# RF_433MHz.net
KiCad netlist of a schematic drawn in Altium Designer
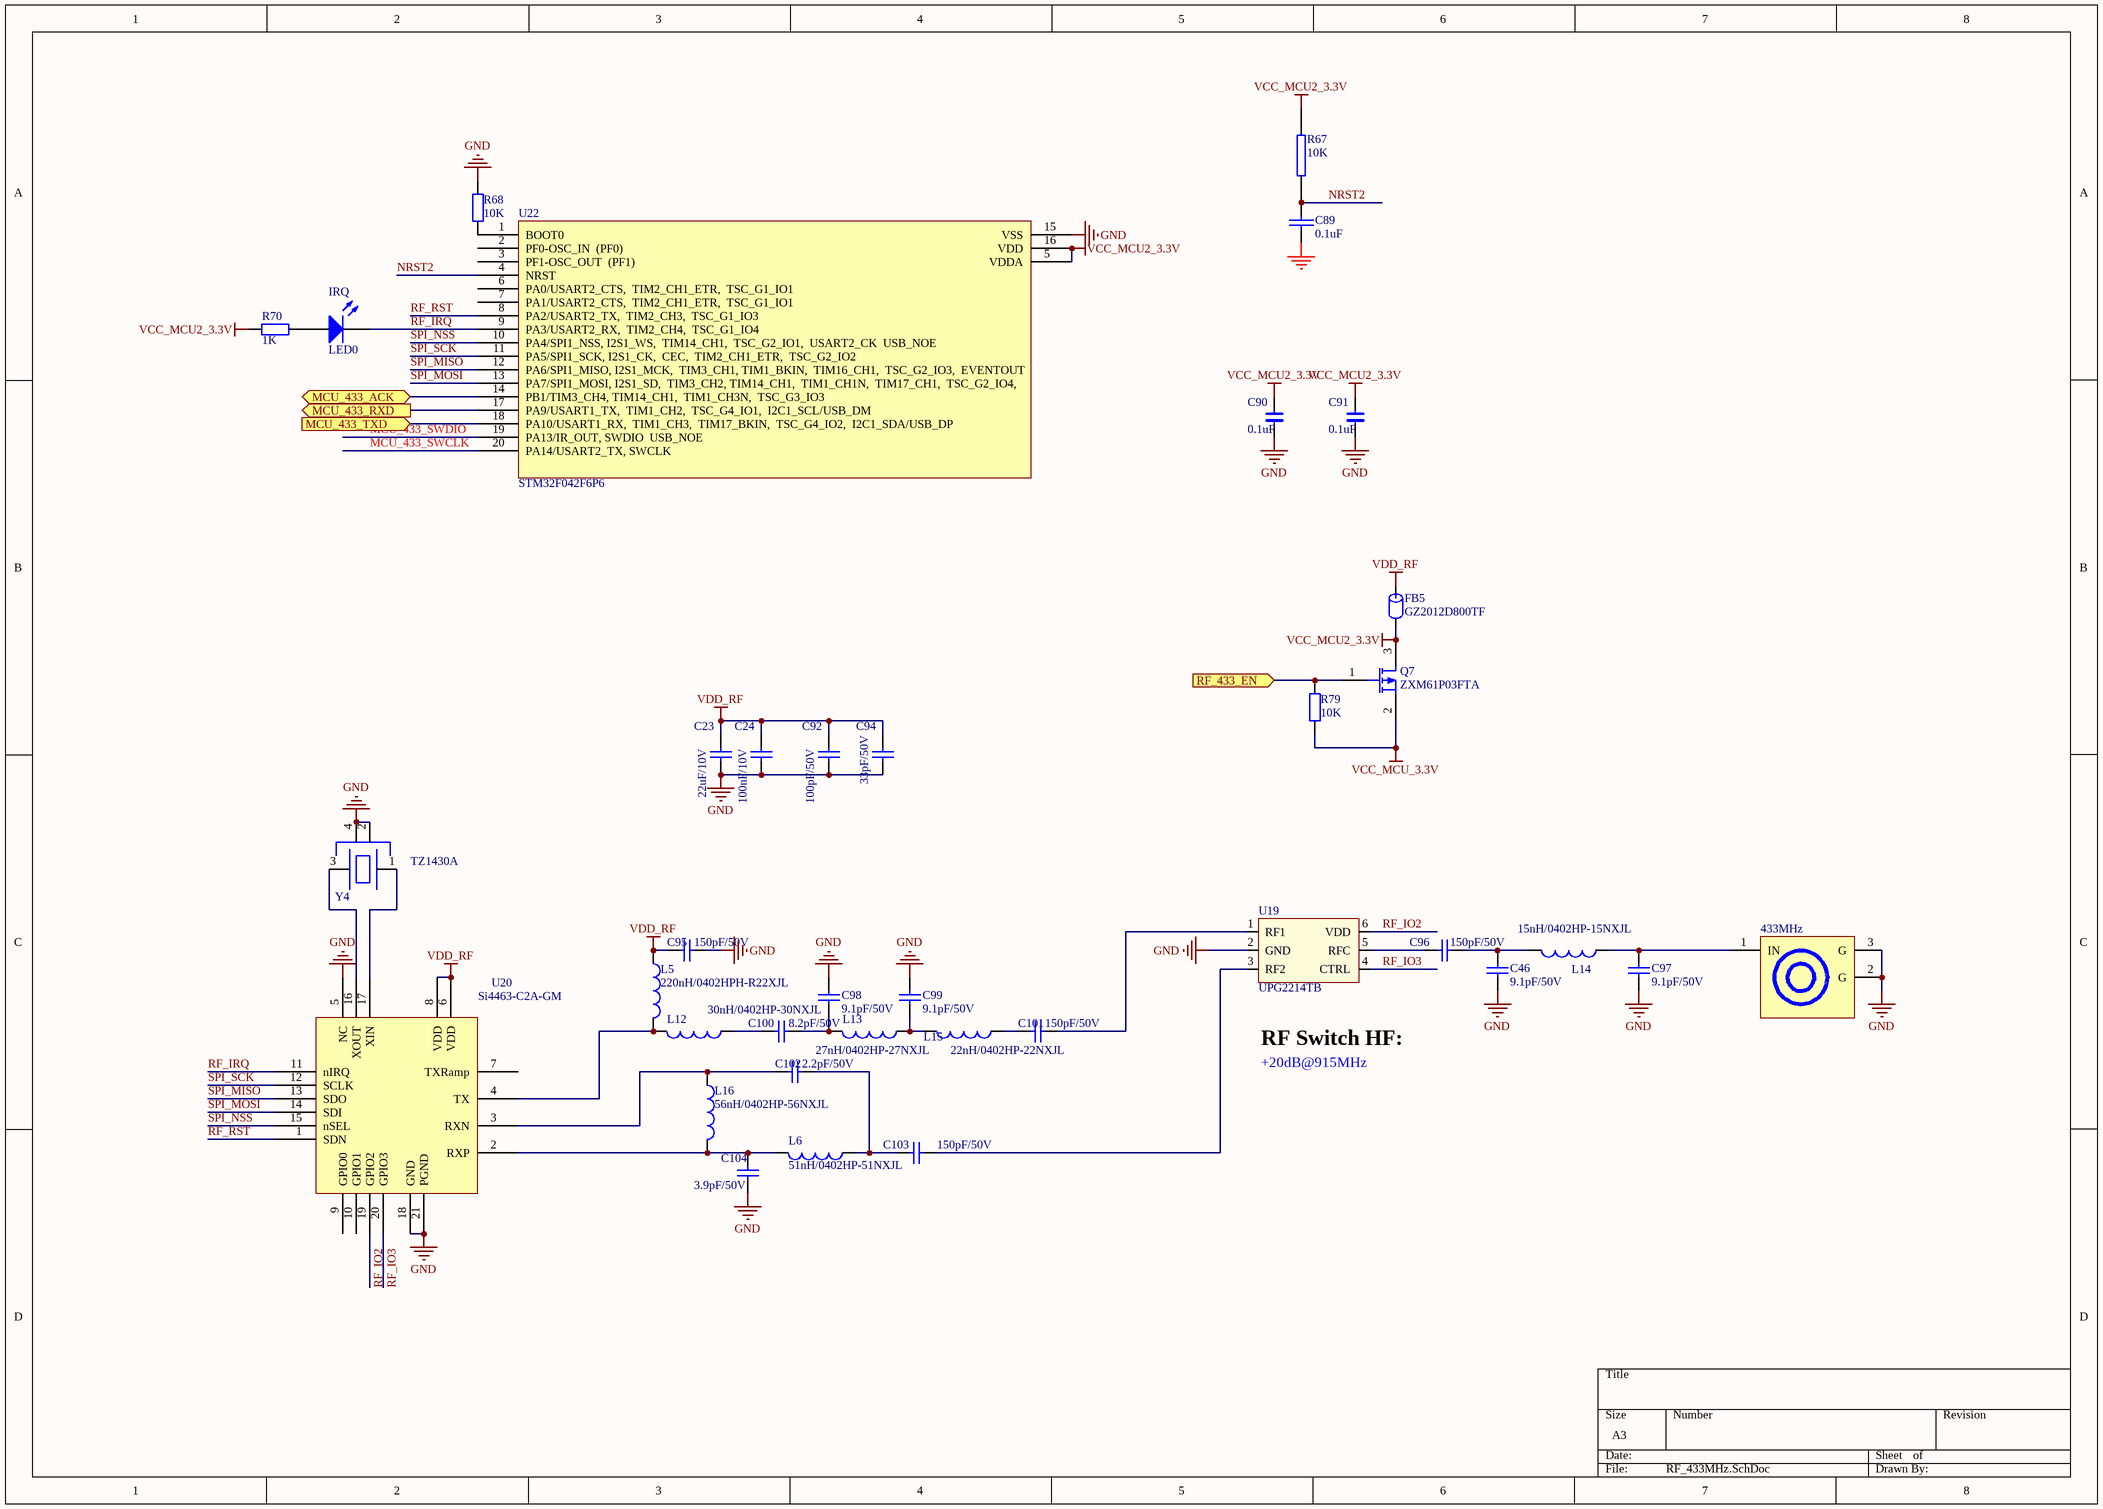
[diagram p0: RF_433MHz.SchDoc]

(export (version "E")
  (design (tool "Eeschema 10.0.6"))
  (components
    (comp (ref "433MHz")
      (value "IPX")
      (footprint "Pcblib_20110825:ECT8180001581")
      (description "MCU")
      (libsource (lib "MCU") (part "IPX"))
    )
    (comp (ref "C23")
      (value "22uF/10V")
      (footprint "0805C")
      (description "Capacitor (Semiconductor SIM Model)")
      (fields (field (name "PUBLISHER") "Altium Limited"))
      (libsource (lib "SX1276_e266v02a") (part "Cap Semi"))
    )
    (comp (ref "C24")
      (value "100nF/10V")
      (footprint "0603C")
      (description "Capacitor (Semiconductor SIM Model)")
      (fields (field (name "PUBLISHER") "Altium Limited"))
      (libsource (lib "SX1276_e266v02a") (part "Cap Semi"))
    )
    (comp (ref "C46")
      (value "9.1pF/50V")
      (footprint "0402C")
      (description "Capacitor SMD")
      (fields (field (name "PUBLISHER") "Altium Limited"))
      (libsource (lib "SX1276_e266v02a") (part "Cap"))
    )
    (comp (ref "C89")
      (value "0.1uF")
      (footprint "0603C")
      (description "Capacitor")
      (libsource (lib "*") (part "CAP"))
    )
    (comp (ref "C90")
      (value "0.1uF")
      (footprint "0603C")
      (description "C")
      (libsource (lib "Schlib_20110825") (part "C"))
    )
    (comp (ref "C91")
      (value "0.1uF")
      (footprint "0603C")
      (description "C")
      (libsource (lib "Schlib_20110825") (part "C"))
    )
    (comp (ref "C92")
      (value "100pF/50V")
      (footprint "0603C")
      (description "Capacitor (Semiconductor SIM Model)")
      (fields (field (name "PUBLISHER") "Altium Limited"))
      (libsource (lib "SX1276_e266v02a") (part "Cap Semi"))
    )
    (comp (ref "C94")
      (value "33pF/50V")
      (footprint "0603C")
      (description "Capacitor (Semiconductor SIM Model)")
      (fields (field (name "PUBLISHER") "Altium Limited"))
      (libsource (lib "SX1276_e266v02a") (part "Cap Semi"))
    )
    (comp (ref "C95")
      (value "150pF/50V")
      (footprint "0402C")
      (description "Capacitor SMD")
      (fields (field (name "PUBLISHER") "Altium Limited"))
      (libsource (lib "SX1276_e266v02a") (part "Cap"))
    )
    (comp (ref "C96")
      (value "150pF/50V")
      (footprint "0402C")
      (description "Capacitor SMD")
      (fields (field (name "PUBLISHER") "Altium Limited"))
      (libsource (lib "SX1276_e266v02a") (part "Cap"))
    )
    (comp (ref "C97")
      (value "9.1pF/50V")
      (footprint "0402C")
      (description "Capacitor SMD")
      (fields (field (name "PUBLISHER") "Altium Limited"))
      (libsource (lib "SX1276_e266v02a") (part "Cap"))
    )
    (comp (ref "C98")
      (value "9.1pF/50V")
      (footprint "0402C")
      (description "Capacitor SMD")
      (fields (field (name "PUBLISHER") "Altium Limited"))
      (libsource (lib "SX1276_e266v02a") (part "Cap"))
    )
    (comp (ref "C99")
      (value "9.1pF/50V")
      (footprint "0402C")
      (description "Capacitor SMD")
      (fields (field (name "PUBLISHER") "Altium Limited"))
      (libsource (lib "SX1276_e266v02a") (part "Cap"))
    )
    (comp (ref "C100")
      (value "8.2pF/50V")
      (footprint "0402C")
      (description "Capacitor SMD")
      (fields (field (name "PUBLISHER") "Altium Limited"))
      (libsource (lib "SX1276_e266v02a") (part "Cap"))
    )
    (comp (ref "C101")
      (value "150pF/50V")
      (footprint "0402C")
      (description "Capacitor SMD")
      (fields (field (name "PUBLISHER") "Altium Limited"))
      (libsource (lib "SX1276_e266v02a") (part "Cap"))
    )
    (comp (ref "C102")
      (value "2.2pF/50V")
      (footprint "0402C")
      (description "Capacitor SMD")
      (fields (field (name "PUBLISHER") "Altium Limited"))
      (libsource (lib "SX1276_e266v02a") (part "Cap"))
    )
    (comp (ref "C103")
      (value "150pF/50V")
      (footprint "0402C")
      (description "Capacitor SMD")
      (fields (field (name "PUBLISHER") "Altium Limited"))
      (libsource (lib "SX1276_e266v02a") (part "Cap"))
    )
    (comp (ref "C104")
      (value "3.9pF/50V")
      (footprint "0402C")
      (description "Capacitor SMD")
      (fields (field (name "PUBLISHER") "Altium Limited"))
      (libsource (lib "SX1276_e266v02a") (part "Cap"))
    )
    (comp (ref "FB5")
      (value "GZ2012D800TF")
      (footprint "0805CZ")
      (libsource (lib "Schlib_20110825") (part "FB"))
    )
    (comp (ref "IRQ")
      (value "LED0")
      (footprint "0603LED")
      (description "Typical INFRARED GaAs LED")
      (fields (field (name "PUBLISHER") "Altium Limited"))
      (libsource (lib "Miscellaneous Devices") (part "LED0"))
    )
    (comp (ref "L5")
      (value "220nH/0402HPH-R22XJL")
      (footprint "0402R")
      (description "Inductor SMD")
      (fields (field (name "PUBLISHER") "Altium Limited"))
      (libsource (lib "SX1276_e266v02a") (part "Inductor"))
    )
    (comp (ref "L6")
      (value "51nH/0402HP-51NXJL")
      (footprint "0402R")
      (description "Inductor SMD")
      (fields (field (name "PUBLISHER") "Altium Limited"))
      (libsource (lib "SX1276_e266v02a") (part "Inductor"))
    )
    (comp (ref "L12")
      (value "30nH/0402HP-30NXJL")
      (footprint "0402R")
      (description "Inductor SMD")
      (fields (field (name "PUBLISHER") "Altium Limited"))
      (libsource (lib "SX1276_e266v02a") (part "Inductor"))
    )
    (comp (ref "L13")
      (value "27nH/0402HP-27NXJL")
      (footprint "0402R")
      (description "Inductor SMD")
      (fields (field (name "PUBLISHER") "Altium Limited"))
      (libsource (lib "SX1276_e266v02a") (part "Inductor"))
    )
    (comp (ref "L14")
      (value "15nH/0402HP-15NXJL")
      (footprint "0402R")
      (description "Inductor SMD")
      (fields (field (name "PUBLISHER") "Altium Limited"))
      (libsource (lib "SX1276_e266v02a") (part "Inductor"))
    )
    (comp (ref "L15")
      (value "22nH/0402HP-22NXJL")
      (footprint "0402R")
      (description "Inductor SMD")
      (fields (field (name "PUBLISHER") "Altium Limited"))
      (libsource (lib "SX1276_e266v02a") (part "Inductor"))
    )
    (comp (ref "L16")
      (value "56nH/0402HP-56NXJL")
      (footprint "0402R")
      (description "Inductor SMD")
      (fields (field (name "PUBLISHER") "Altium Limited"))
      (libsource (lib "SX1276_e266v02a") (part "Inductor"))
    )
    (comp (ref "Q7")
      (value "ZXM61P03FTA")
      (footprint "SOT23-3")
      (description "ZXM61P03F")
      (fields (field (name "PUBLISHER") "Altium Limited"))
      (libsource (lib "Miscellaneous Devices") (part "MOSFET-P"))
    )
    (comp (ref "R67") (value "10K") (footprint "0603R") (libsource (lib "*") (part "RES2")))
    (comp (ref "R68")
      (value "10K")
      (footprint "0603R")
      (description "Resistor")
      (fields (field (name "PUBLISHER") "Altium Limited"))
      (libsource (lib "") (part "Res2_1"))
    )
    (comp (ref "R70")
      (value "1K")
      (footprint "0603R")
      (description "Resistor")
      (fields (field (name "PUBLISHER") "Altium Limited"))
      (libsource (lib "") (part "Res2_2"))
    )
    (comp (ref "R79")
      (value "10K")
      (footprint "0603R")
      (description "Resistor")
      (fields (field (name "PUBLISHER") "Altium Limited"))
      (libsource (lib "Miscellaneous Devices") (part "Res2"))
    )
    (comp (ref "U19")
      (value "UPG2214TB")
      (footprint "SC70-6")
      (description "PE4259 Peregrine RF Switch")
      (libsource (lib "SX1276_e266v02a") (part "PE4259 RF Switch"))
    )
    (comp (ref "U20")
      (value "Si4463-C2A-GM")
      (footprint "QFN50P400X400X80-20N")
      (libsource (lib "stm32") (part "Si4463"))
    )
    (comp (ref "U22")
      (value "STM32F042F6P6")
      (footprint "SOP65P640X265-20N")
      (libsource (lib "stm32") (part "STM32F042F6P6"))
    )
    (comp (ref "Y4")
      (value "TZ1430A")
      (footprint "OSCILLATOR-2.5X2.0")
      (libsource (lib "Myself_1") (part "XTAL3"))
    )
  )
  (nets
    (net (code "1") (name "/MCU_433_ACK") (class "Default")
      (node (ref "U22") (pin "14") (pinfunction "PB1/TIM3_CH4,_TIM14_CH1,__TIM1_CH3N,__TSC_G3_IO3_14") (pintype "passive"))
    )
    (net (code "2") (name "/MCU_433_RXD") (class "Default")
      (node (ref "U22") (pin "17") (pinfunction "PA9/USART1_TX,__TIM1_CH2,__TSC_G4_IO1,__I2C1_SCL/USB_DM_17") (pintype "passive"))
    )
    (net (code "3") (name "/MCU_433_SWCLK") (class "Default")
      (node (ref "U22") (pin "20") (pinfunction "PA14/USART2_TX,_SWCLK_20") (pintype "passive"))
    )
    (net (code "4") (name "/MCU_433_SWDIO") (class "Default")
      (node (ref "U22") (pin "19") (pinfunction "PA13/IR_OUT,_SWDIO__USB_NOE_19") (pintype "passive"))
    )
    (net (code "5") (name "/MCU_433_TXD") (class "Default")
      (node (ref "U22") (pin "18") (pinfunction "PA10/USART1_RX,__TIM1_CH3,__TIM17_BKIN,__TSC_G4_IO2,__I2C1_SDA/USB_DP_18") (pintype "passive"))
    )
    (net (code "6") (name "/NRST2") (class "Default")
      (node (ref "C89") (pin "1") (pinfunction "1_1") (pintype "passive"))
      (node (ref "R67") (pin "2") (pinfunction "2_2") (pintype "passive"))
      (node (ref "U22") (pin "4") (pinfunction "NRST_4") (pintype "passive"))
    )
    (net (code "7") (name "/RF_433_EN") (class "Default")
      (node (ref "Q7") (pin "1") (pinfunction "G_1") (pintype "passive"))
      (node (ref "R79") (pin "1") (pinfunction "1_1") (pintype "passive"))
    )
    (net (code "8") (name "/RF_IO2") (class "Default")
      (node (ref "U19") (pin "6") (pinfunction "VDD_6") (pintype "passive"))
      (node (ref "U20") (pin "19") (pinfunction "GPIO2_19") (pintype "passive"))
    )
    (net (code "9") (name "/RF_IO3") (class "Default")
      (node (ref "U19") (pin "4") (pinfunction "CTRL_4") (pintype "passive"))
      (node (ref "U20") (pin "20") (pinfunction "GPIO3_20") (pintype "passive"))
    )
    (net (code "10") (name "/RF_IRQ") (class "Default")
      (node (ref "IRQ") (pin "2") (pinfunction "K_2") (pintype "passive"))
      (node (ref "U20") (pin "11") (pinfunction "nIRQ_11") (pintype "passive"))
      (node (ref "U22") (pin "9") (pinfunction "PA3/USART2_RX,__TIM2_CH4,__TSC_G1_IO4_9") (pintype "passive"))
    )
    (net (code "11") (name "/RF_RST") (class "Default")
      (node (ref "U20") (pin "1") (pinfunction "SDN_1") (pintype "passive"))
      (node (ref "U22") (pin "8") (pinfunction "PA2/USART2_TX,__TIM2_CH3,__TSC_G1_IO3_8") (pintype "passive"))
    )
    (net (code "12") (name "/SPI_MISO") (class "Default")
      (node (ref "U20") (pin "13") (pinfunction "SDO_13") (pintype "passive"))
      (node (ref "U22") (pin "12") (pinfunction "PA6/SPI1_MISO,_I2S1_MCK,__TIM3_CH1,_TIM1_BKIN,__TIM16_CH1,__TSC_G2_IO3,__EVENTOUT_12") (pintype "passive"))
    )
    (net (code "13") (name "/SPI_MOSI") (class "Default")
      (node (ref "U20") (pin "14") (pinfunction "SDI_14") (pintype "passive"))
      (node (ref "U22") (pin "13") (pinfunction "PA7/SPI1_MOSI,_I2S1_SD,__TIM3_CH2,_TIM14_CH1,__TIM1_CH1N,__TIM17_CH1,__TSC_G2_IO4,_13") (pintype "passive"))
    )
    (net (code "14") (name "/SPI_NSS") (class "Default")
      (node (ref "U20") (pin "15") (pinfunction "nSEL_15") (pintype "passive"))
      (node (ref "U22") (pin "10") (pinfunction "PA4/SPI1_NSS,_I2S1_WS,__TIM14_CH1,__TSC_G2_IO1,__USART2_CK__USB_NOE_10") (pintype "passive"))
    )
    (net (code "15") (name "/SPI_SCK") (class "Default")
      (node (ref "U20") (pin "12") (pinfunction "SCLK_12") (pintype "passive"))
      (node (ref "U22") (pin "11") (pinfunction "PA5/SPI1_SCK,_I2S1_CK,__CEC,__TIM2_CH1_ETR,__TSC_G2_IO2_11") (pintype "passive"))
    )
    (net (code "16") (name "GND") (class "Default")
      (node (ref "433MHz") (pin "2") (pinfunction "G_2") (pintype "passive"))
      (node (ref "433MHz") (pin "3") (pinfunction "G_3") (pintype "passive"))
      (node (ref "C104") (pin "1") (pinfunction "1_1") (pintype "passive"))
      (node (ref "C23") (pin "1") (pinfunction "1_1") (pintype "passive"))
      (node (ref "C24") (pin "1") (pinfunction "1_1") (pintype "passive"))
      (node (ref "C46") (pin "1") (pinfunction "1_1") (pintype "passive"))
      (node (ref "C89") (pin "2") (pinfunction "2_2") (pintype "passive"))
      (node (ref "C90") (pin "1") (pintype "passive"))
      (node (ref "C91") (pin "1") (pintype "passive"))
      (node (ref "C92") (pin "1") (pinfunction "1_1") (pintype "passive"))
      (node (ref "C94") (pin "1") (pinfunction "1_1") (pintype "passive"))
      (node (ref "C95") (pin "2") (pinfunction "2_2") (pintype "passive"))
      (node (ref "C97") (pin "1") (pinfunction "1_1") (pintype "passive"))
      (node (ref "C98") (pin "2") (pinfunction "2_2") (pintype "passive"))
      (node (ref "C99") (pin "2") (pinfunction "2_2") (pintype "passive"))
      (node (ref "R68") (pin "2") (pinfunction "2_2") (pintype "passive"))
      (node (ref "U19") (pin "2") (pinfunction "GND_2") (pintype "passive"))
      (node (ref "U20") (pin "18") (pinfunction "GND_18") (pintype "passive"))
      (node (ref "U20") (pin "21") (pinfunction "PGND_21") (pintype "passive"))
      (node (ref "U20") (pin "5") (pinfunction "NC_5") (pintype "passive"))
      (node (ref "U22") (pin "15") (pinfunction "VSS_15") (pintype "passive"))
      (node (ref "Y4") (pin "2") (pinfunction "GND_2") (pintype "passive"))
      (node (ref "Y4") (pin "4") (pinfunction "GND_4") (pintype "passive"))
    )
    (net (code "17") (name "Net-(433MHz-IN)") (class "Default")
      (node (ref "433MHz") (pin "1") (pinfunction "IN_1") (pintype "passive"))
      (node (ref "C97") (pin "2") (pinfunction "2_2") (pintype "passive"))
      (node (ref "L14") (pin "1") (pinfunction "1_1") (pintype "passive"))
    )
    (net (code "18") (name "Net-(C46-Pad2)") (class "Default")
      (node (ref "C46") (pin "2") (pinfunction "2_2") (pintype "passive"))
      (node (ref "C96") (pin "1") (pinfunction "1_1") (pintype "passive"))
      (node (ref "L14") (pin "2") (pinfunction "2_2") (pintype "passive"))
    )
    (net (code "19") (name "Net-(C99-Pad1)") (class "Default")
      (node (ref "C99") (pin "1") (pinfunction "1_1") (pintype "passive"))
      (node (ref "L13") (pin "1") (pinfunction "1_1") (pintype "passive"))
      (node (ref "L15") (pin "2") (pinfunction "2_2") (pintype "passive"))
    )
    (net (code "20") (name "Net-(C100-Pad1)") (class "Default")
      (node (ref "C100") (pin "1") (pinfunction "1_1") (pintype "passive"))
      (node (ref "L12") (pin "1") (pinfunction "1_1") (pintype "passive"))
    )
    (net (code "21") (name "Net-(C100-Pad2)") (class "Default")
      (node (ref "C100") (pin "2") (pinfunction "2_2") (pintype "passive"))
      (node (ref "C98") (pin "1") (pinfunction "1_1") (pintype "passive"))
      (node (ref "L13") (pin "2") (pinfunction "2_2") (pintype "passive"))
    )
    (net (code "22") (name "Net-(C101-Pad2)") (class "Default")
      (node (ref "C101") (pin "2") (pinfunction "2_2") (pintype "passive"))
      (node (ref "L15") (pin "1") (pinfunction "1_1") (pintype "passive"))
    )
    (net (code "23") (name "Net-(C102-Pad2)") (class "Default")
      (node (ref "C102") (pin "2") (pinfunction "2_2") (pintype "passive"))
      (node (ref "C103") (pin "1") (pinfunction "1_1") (pintype "passive"))
      (node (ref "L6") (pin "1") (pinfunction "1_1") (pintype "passive"))
    )
    (net (code "24") (name "Net-(IRQ-A)") (class "Default")
      (node (ref "IRQ") (pin "1") (pinfunction "A_1") (pintype "passive"))
      (node (ref "R70") (pin "2") (pinfunction "2_2") (pintype "passive"))
    )
    (net (code "25") (name "Net-(U19-RF1)") (class "Default")
      (node (ref "C101") (pin "1") (pinfunction "1_1") (pintype "passive"))
      (node (ref "U19") (pin "1") (pinfunction "RF1_1") (pintype "passive"))
    )
    (net (code "26") (name "Net-(U19-RF2)") (class "Default")
      (node (ref "C103") (pin "2") (pinfunction "2_2") (pintype "passive"))
      (node (ref "U19") (pin "3") (pinfunction "RF2_3") (pintype "passive"))
    )
    (net (code "27") (name "Net-(U19-RFC)") (class "Default")
      (node (ref "C96") (pin "2") (pinfunction "2_2") (pintype "passive"))
      (node (ref "U19") (pin "5") (pinfunction "RFC_5") (pintype "passive"))
    )
    (net (code "28") (name "Net-(U20-RXN)") (class "Default")
      (node (ref "C102") (pin "1") (pinfunction "1_1") (pintype "passive"))
      (node (ref "L16") (pin "1") (pinfunction "1_1") (pintype "passive"))
      (node (ref "U20") (pin "3") (pinfunction "RXN_3") (pintype "passive"))
    )
    (net (code "29") (name "Net-(U20-RXP)") (class "Default")
      (node (ref "C104") (pin "2") (pinfunction "2_2") (pintype "passive"))
      (node (ref "L16") (pin "2") (pinfunction "2_2") (pintype "passive"))
      (node (ref "L6") (pin "2") (pinfunction "2_2") (pintype "passive"))
      (node (ref "U20") (pin "2") (pinfunction "RXP_2") (pintype "passive"))
    )
    (net (code "30") (name "Net-(U20-TX)") (class "Default")
      (node (ref "L12") (pin "2") (pinfunction "2_2") (pintype "passive"))
      (node (ref "L5") (pin "2") (pinfunction "2_2") (pintype "passive"))
      (node (ref "U20") (pin "4") (pinfunction "TX_4") (pintype "passive"))
    )
    (net (code "31") (name "Net-(U20-XIN)") (class "Default")
      (node (ref "U20") (pin "17") (pinfunction "XIN_17") (pintype "passive"))
      (node (ref "Y4") (pin "1") (pinfunction "1_1") (pintype "passive"))
    )
    (net (code "32") (name "Net-(U20-XOUT)") (class "Default")
      (node (ref "U20") (pin "16") (pinfunction "XOUT_16") (pintype "passive"))
      (node (ref "Y4") (pin "3") (pinfunction "3_3") (pintype "passive"))
    )
    (net (code "33") (name "Net-(U22-BOOT0)") (class "Default")
      (node (ref "R68") (pin "1") (pinfunction "1_1") (pintype "passive"))
      (node (ref "U22") (pin "1") (pinfunction "BOOT0_1") (pintype "passive"))
    )
    (net (code "34") (name "VCC_MCU2_3.3V") (class "Default")
      (node (ref "C90") (pin "2") (pintype "passive"))
      (node (ref "C91") (pin "2") (pintype "passive"))
      (node (ref "FB5") (pin "2") (pintype "passive"))
      (node (ref "Q7") (pin "3") (pinfunction "S_3") (pintype "passive"))
      (node (ref "R67") (pin "1") (pinfunction "1_1") (pintype "passive"))
      (node (ref "R70") (pin "1") (pinfunction "1_1") (pintype "passive"))
      (node (ref "U22") (pin "16") (pinfunction "VDD_16") (pintype "passive"))
      (node (ref "U22") (pin "5") (pinfunction "VDDA_5") (pintype "passive"))
    )
    (net (code "35") (name "VCC_MCU_3.3V") (class "Default")
      (node (ref "Q7") (pin "2") (pinfunction "D_2") (pintype "passive"))
      (node (ref "R79") (pin "2") (pinfunction "2_2") (pintype "passive"))
    )
    (net (code "36") (name "VDD_RF") (class "Default")
      (node (ref "C23") (pin "2") (pinfunction "2_2") (pintype "passive"))
      (node (ref "C24") (pin "2") (pinfunction "2_2") (pintype "passive"))
      (node (ref "C92") (pin "2") (pinfunction "2_2") (pintype "passive"))
      (node (ref "C94") (pin "2") (pinfunction "2_2") (pintype "passive"))
      (node (ref "C95") (pin "1") (pinfunction "1_1") (pintype "passive"))
      (node (ref "FB5") (pin "1") (pintype "passive"))
      (node (ref "L5") (pin "1") (pinfunction "1_1") (pintype "passive"))
      (node (ref "U20") (pin "6") (pinfunction "VDD_6") (pintype "passive"))
      (node (ref "U20") (pin "8") (pinfunction "VDD_8") (pintype "passive"))
    )
    (net (code "37") (name "unconnected-(U20-GPIO0-Pad9)") (class "Default")
      (node (ref "U20") (pin "9") (pinfunction "GPIO0_9") (pintype "passive"))
    )
    (net (code "38") (name "unconnected-(U20-GPIO1-Pad10)") (class "Default")
      (node (ref "U20") (pin "10") (pinfunction "GPIO1_10") (pintype "passive"))
    )
    (net (code "39") (name "unconnected-(U20-TXRamp-Pad7)") (class "Default")
      (node (ref "U20") (pin "7") (pinfunction "TXRamp_7") (pintype "passive"))
    )
    (net (code "40") (name "unconnected-(U22-PA0{slash}USART2_CTS,__TIM2_CH1_ETR,__TSC_G1_IO1-Pad6)") (class "Default")
      (node (ref "U22") (pin "6") (pinfunction "PA0/USART2_CTS,__TIM2_CH1_ETR,__TSC_G1_IO1_6") (pintype "passive"))
    )
    (net (code "41") (name "unconnected-(U22-PA1{slash}USART2_CTS,__TIM2_CH1_ETR,__TSC_G1_IO1-Pad7)") (class "Default")
      (node (ref "U22") (pin "7") (pinfunction "PA1/USART2_CTS,__TIM2_CH1_ETR,__TSC_G1_IO1_7") (pintype "passive"))
    )
    (net (code "42") (name "unconnected-(U22-PF0-OSC_IN__(PF0)-Pad2)") (class "Default")
      (node (ref "U22") (pin "2") (pinfunction "PF0-OSC_IN__(PF0)_2") (pintype "passive"))
    )
    (net (code "43") (name "unconnected-(U22-PF1-OSC_OUT__(PF1)-Pad3)") (class "Default")
      (node (ref "U22") (pin "3") (pinfunction "PF1-OSC_OUT__(PF1)_3") (pintype "passive"))
    )
  )
)
